# SFXboard.net
KiCad netlist of a schematic drawn in EAGLE
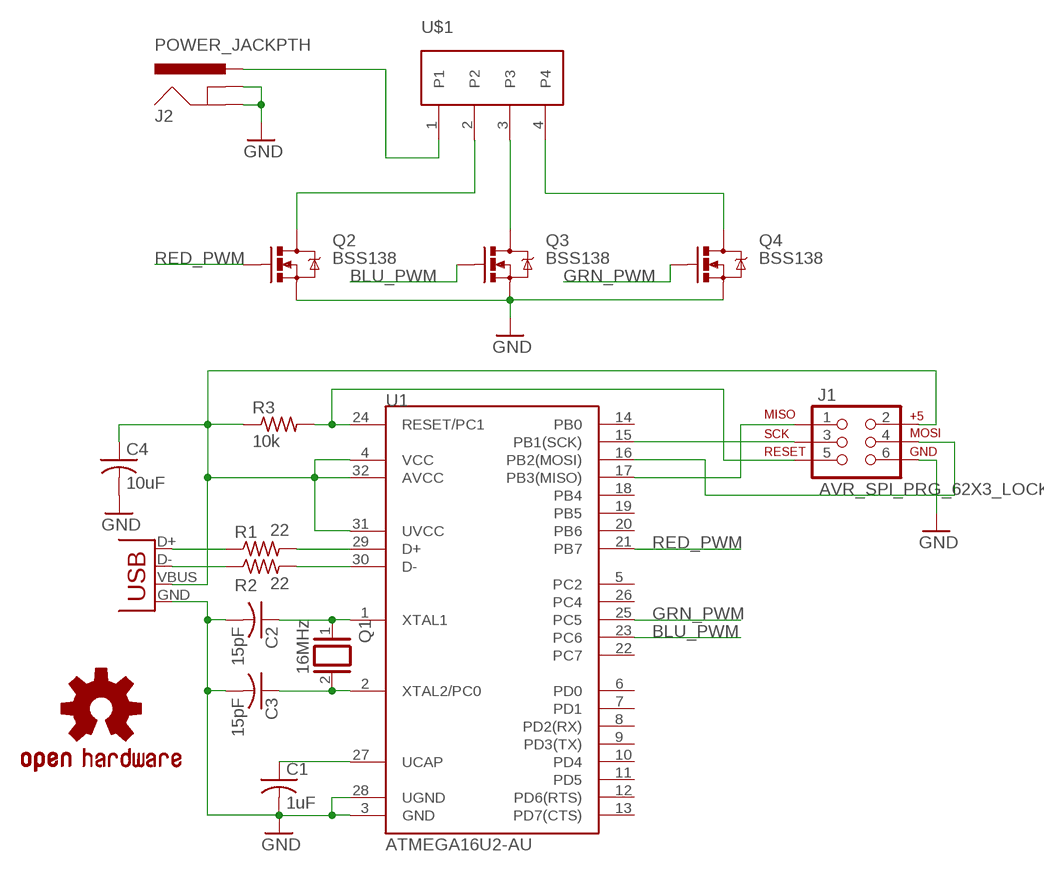
[diagram p0: schematic, sheet 1]

(export (version "E")
  (design (tool "Eeschema 10.0.6"))
  (components
    (comp (ref "C1")
      (value "1uF")
      (footprint "eagle-import:C0805")
      (libsource (lib "eagle-import") (part "C-USC0805"))
    )
    (comp (ref "C2")
      (value "15pF")
      (footprint "eagle-import:C0805")
      (libsource (lib "eagle-import") (part "C-USC0805"))
    )
    (comp (ref "C3")
      (value "15pF")
      (footprint "eagle-import:C0805")
      (libsource (lib "eagle-import") (part "C-USC0805"))
    )
    (comp (ref "C4")
      (value "10uF")
      (footprint "eagle-import:C0805")
      (libsource (lib "eagle-import") (part "C-USC0805"))
    )
    (comp (ref "J1")
      (value "AVR_SPI_PRG_62X3_LOCK")
      (footprint "eagle-import:2X3_LOCK")
      (libsource (lib "eagle-import") (part "AVR_SPI_PRG_62X3_LOCK"))
    )
    (comp (ref "J2")
      (value "POWER_JACKPTH")
      (footprint "eagle-import:POWER_JACK_PTH")
      (libsource (lib "eagle-import") (part "POWER_JACKPTH"))
    )
    (comp (ref "Q1")
      (value "16MHz")
      (footprint "eagle-import:QS")
      (libsource (lib "eagle-import") (part "XTAL/S"))
    )
    (comp (ref "Q2")
      (value "BSS138")
      (footprint "eagle-import:SOT23-3")
      (libsource (lib "eagle-import") (part "BSS138TRANS-00830"))
    )
    (comp (ref "Q3")
      (value "BSS138")
      (footprint "eagle-import:SOT23-3")
      (libsource (lib "eagle-import") (part "BSS138TRANS-00830"))
    )
    (comp (ref "Q4")
      (value "BSS138")
      (footprint "eagle-import:SOT23-3")
      (libsource (lib "eagle-import") (part "BSS138TRANS-00830"))
    )
    (comp (ref "R1")
      (value "22")
      (footprint "eagle-import:R0805")
      (libsource (lib "eagle-import") (part "R-US_R0805"))
    )
    (comp (ref "R2")
      (value "22")
      (footprint "eagle-import:R0805")
      (libsource (lib "eagle-import") (part "R-US_R0805"))
    )
    (comp (ref "R3")
      (value "10k")
      (footprint "eagle-import:R0805")
      (libsource (lib "eagle-import") (part "R-US_R0805"))
    )
    (comp (ref "U$1")
      (value "TERMBLOCK4POS")
      (footprint "eagle-import:TERMBLOCK4P")
      (libsource (lib "eagle-import") (part "TERMBLOCK4POS"))
    )
    (comp (ref "U$2")
      (value "OSHW-LOGOS")
      (footprint "eagle-import:OSHW-LOGO-S")
      (libsource (lib "eagle-import") (part "OSHW-LOGOS"))
    )
    (comp (ref "U1")
      (value "ATMEGA16U2-AU")
      (footprint "eagle-import:TQFP32-08")
      (libsource (lib "eagle-import") (part "ATMEGA8U2AU"))
    )
    (comp (ref "X1")
      (value "USBSMD")
      (footprint "eagle-import:USB-MINIB")
      (libsource (lib "eagle-import") (part "USBSMD"))
    )
  )
  (nets
    (net (code "1") (name "/BLU_PWM") (class "Default")
      (node (ref "Q3") (pin "1") (pinfunction "G_1") (pintype "passive"))
      (node (ref "U1") (pin "23") (pinfunction "PC6_23") (pintype "bidirectional"))
    )
    (net (code "2") (name "/GRN_PWM") (class "Default")
      (node (ref "Q4") (pin "1") (pinfunction "G_1") (pintype "passive"))
      (node (ref "U1") (pin "25") (pinfunction "PC5_25") (pintype "bidirectional"))
    )
    (net (code "3") (name "/RED_PWM") (class "Default")
      (node (ref "Q2") (pin "1") (pinfunction "G_1") (pintype "passive"))
      (node (ref "U1") (pin "21") (pinfunction "PB7_21") (pintype "bidirectional"))
    )
    (net (code "4") (name "GND") (class "Default")
      (node (ref "C1") (pin "2") (pinfunction "2_2") (pintype "passive"))
      (node (ref "C2") (pin "2") (pinfunction "2_2") (pintype "passive"))
      (node (ref "C3") (pin "2") (pinfunction "2_2") (pintype "passive"))
      (node (ref "C4") (pin "2") (pinfunction "2_2") (pintype "passive"))
      (node (ref "J1") (pin "6") (pinfunction "6_6") (pintype "passive"))
      (node (ref "J2") (pin "GND") (pinfunction "GND_GND") (pintype "bidirectional"))
      (node (ref "J2") (pin "GNDBREAK") (pinfunction "GNDBREAK_GNDBREAK") (pintype "bidirectional"))
      (node (ref "Q2") (pin "2") (pinfunction "S_2") (pintype "passive"))
      (node (ref "Q3") (pin "2") (pinfunction "S_2") (pintype "passive"))
      (node (ref "Q4") (pin "2") (pinfunction "S_2") (pintype "passive"))
      (node (ref "U1") (pin "28") (pinfunction "UGND_28") (pintype "bidirectional"))
      (node (ref "U1") (pin "3") (pinfunction "GND_3") (pintype "bidirectional"))
      (node (ref "X1") (pin "GND") (pinfunction "GND_GND") (pintype "bidirectional"))
    )
    (net (code "5") (name "Net-(Q2-D)") (class "Default")
      (node (ref "Q2") (pin "3") (pinfunction "D_3") (pintype "passive"))
      (node (ref "U$1") (pin "2") (pinfunction "P2_2") (pintype "bidirectional"))
    )
    (net (code "6") (name "Net-(Q3-D)") (class "Default")
      (node (ref "Q3") (pin "3") (pinfunction "D_3") (pintype "passive"))
      (node (ref "U$1") (pin "3") (pinfunction "P3_3") (pintype "bidirectional"))
    )
    (net (code "7") (name "Net-(Q4-D)") (class "Default")
      (node (ref "Q4") (pin "3") (pinfunction "D_3") (pintype "passive"))
      (node (ref "U$1") (pin "4") (pinfunction "P4_4") (pintype "bidirectional"))
    )
    (net (code "8") (name "Net-(R1-Pad1)") (class "Default")
      (node (ref "R1") (pin "1") (pinfunction "1_1") (pintype "passive"))
      (node (ref "X1") (pin "D+") (pinfunction "D+_D+") (pintype "bidirectional"))
    )
    (net (code "9") (name "Net-(R2-Pad1)") (class "Default")
      (node (ref "R2") (pin "1") (pinfunction "1_1") (pintype "passive"))
      (node (ref "X1") (pin "D-") (pinfunction "D-_D-") (pintype "bidirectional"))
    )
    (net (code "10") (name "Net-(U$1-P1)") (class "Default")
      (node (ref "J2") (pin "PWR") (pinfunction "PWR_PWR") (pintype "bidirectional"))
      (node (ref "U$1") (pin "1") (pinfunction "P1_1") (pintype "bidirectional"))
    )
    (net (code "11") (name "Net-(U1-AVCC)") (class "Default")
      (node (ref "C4") (pin "1") (pinfunction "1_1") (pintype "passive"))
      (node (ref "J1") (pin "2") (pinfunction "2_2") (pintype "passive"))
      (node (ref "R3") (pin "1") (pinfunction "1_1") (pintype "passive"))
      (node (ref "U1") (pin "31") (pinfunction "UVCC_31") (pintype "bidirectional"))
      (node (ref "U1") (pin "32") (pinfunction "AVCC_32") (pintype "bidirectional"))
      (node (ref "U1") (pin "4") (pinfunction "VCC_4") (pintype "bidirectional"))
      (node (ref "X1") (pin "VBUS") (pinfunction "VBUS_VBUS") (pintype "bidirectional"))
    )
    (net (code "12") (name "Net-(U1-D+)") (class "Default")
      (node (ref "R1") (pin "2") (pinfunction "2_2") (pintype "passive"))
      (node (ref "U1") (pin "29") (pinfunction "D+_29") (pintype "bidirectional"))
    )
    (net (code "13") (name "Net-(U1-D-)") (class "Default")
      (node (ref "R2") (pin "2") (pinfunction "2_2") (pintype "passive"))
      (node (ref "U1") (pin "30") (pinfunction "D-_30") (pintype "bidirectional"))
    )
    (net (code "14") (name "Net-(U1-PB1(SCK))") (class "Default")
      (node (ref "J1") (pin "3") (pinfunction "3_3") (pintype "passive"))
      (node (ref "U1") (pin "15") (pinfunction "PB1(SCK)_15") (pintype "bidirectional"))
    )
    (net (code "15") (name "Net-(U1-PB2(MOSI))") (class "Default")
      (node (ref "J1") (pin "4") (pinfunction "4_4") (pintype "passive"))
      (node (ref "U1") (pin "16") (pinfunction "PB2(MOSI)_16") (pintype "bidirectional"))
    )
    (net (code "16") (name "Net-(U1-PB3(MISO))") (class "Default")
      (node (ref "J1") (pin "1") (pinfunction "1_1") (pintype "passive"))
      (node (ref "U1") (pin "17") (pinfunction "PB3(MISO)_17") (pintype "bidirectional"))
    )
    (net (code "17") (name "Net-(U1-RESET{slash}PC1)") (class "Default")
      (node (ref "J1") (pin "5") (pinfunction "5_5") (pintype "passive"))
      (node (ref "R3") (pin "2") (pinfunction "2_2") (pintype "passive"))
      (node (ref "U1") (pin "24") (pinfunction "RESET/PC1_24") (pintype "bidirectional"))
    )
    (net (code "18") (name "Net-(U1-UCAP)") (class "Default")
      (node (ref "C1") (pin "1") (pinfunction "1_1") (pintype "passive"))
      (node (ref "U1") (pin "27") (pinfunction "UCAP_27") (pintype "bidirectional"))
    )
    (net (code "19") (name "Net-(U1-XTAL1)") (class "Default")
      (node (ref "C2") (pin "1") (pinfunction "1_1") (pintype "passive"))
      (node (ref "Q1") (pin "1") (pinfunction "1_1") (pintype "passive"))
      (node (ref "U1") (pin "1") (pinfunction "XTAL1_1") (pintype "bidirectional"))
    )
    (net (code "20") (name "Net-(U1-XTAL2{slash}PC0)") (class "Default")
      (node (ref "C3") (pin "1") (pinfunction "1_1") (pintype "passive"))
      (node (ref "Q1") (pin "2") (pinfunction "2_2") (pintype "passive"))
      (node (ref "U1") (pin "2") (pinfunction "XTAL2/PC0_2") (pintype "bidirectional"))
    )
    (net (code "21") (name "unconnected-(U1-PB0-Pad14)") (class "Default")
      (node (ref "U1") (pin "14") (pinfunction "PB0_14") (pintype "bidirectional"))
    )
    (net (code "22") (name "unconnected-(U1-PB4-Pad18)") (class "Default")
      (node (ref "U1") (pin "18") (pinfunction "PB4_18") (pintype "bidirectional"))
    )
    (net (code "23") (name "unconnected-(U1-PB5-Pad19)") (class "Default")
      (node (ref "U1") (pin "19") (pinfunction "PB5_19") (pintype "bidirectional"))
    )
    (net (code "24") (name "unconnected-(U1-PB6-Pad20)") (class "Default")
      (node (ref "U1") (pin "20") (pinfunction "PB6_20") (pintype "bidirectional"))
    )
    (net (code "25") (name "unconnected-(U1-PC2-Pad5)") (class "Default")
      (node (ref "U1") (pin "5") (pinfunction "PC2_5") (pintype "bidirectional"))
    )
    (net (code "26") (name "unconnected-(U1-PC4-Pad26)") (class "Default")
      (node (ref "U1") (pin "26") (pinfunction "PC4_26") (pintype "bidirectional"))
    )
    (net (code "27") (name "unconnected-(U1-PC7-Pad22)") (class "Default")
      (node (ref "U1") (pin "22") (pinfunction "PC7_22") (pintype "bidirectional"))
    )
    (net (code "28") (name "unconnected-(U1-PD0-Pad6)") (class "Default")
      (node (ref "U1") (pin "6") (pinfunction "PD0_6") (pintype "bidirectional"))
    )
    (net (code "29") (name "unconnected-(U1-PD1-Pad7)") (class "Default")
      (node (ref "U1") (pin "7") (pinfunction "PD1_7") (pintype "bidirectional"))
    )
    (net (code "30") (name "unconnected-(U1-PD2(RX)-Pad8)") (class "Default")
      (node (ref "U1") (pin "8") (pinfunction "PD2(RX)_8") (pintype "bidirectional"))
    )
    (net (code "31") (name "unconnected-(U1-PD3(TX)-Pad9)") (class "Default")
      (node (ref "U1") (pin "9") (pinfunction "PD3(TX)_9") (pintype "bidirectional"))
    )
    (net (code "32") (name "unconnected-(U1-PD4-Pad10)") (class "Default")
      (node (ref "U1") (pin "10") (pinfunction "PD4_10") (pintype "bidirectional"))
    )
    (net (code "33") (name "unconnected-(U1-PD5-Pad11)") (class "Default")
      (node (ref "U1") (pin "11") (pinfunction "PD5_11") (pintype "bidirectional"))
    )
    (net (code "34") (name "unconnected-(U1-PD6(RTS)-Pad12)") (class "Default")
      (node (ref "U1") (pin "12") (pinfunction "PD6(RTS)_12") (pintype "bidirectional"))
    )
    (net (code "35") (name "unconnected-(U1-PD7(CTS)-Pad13)") (class "Default")
      (node (ref "U1") (pin "13") (pinfunction "PD7(CTS)_13") (pintype "bidirectional"))
    )
  )
)
